# sitrep_display.net
KiCad netlist of a schematic drawn in EAGLE
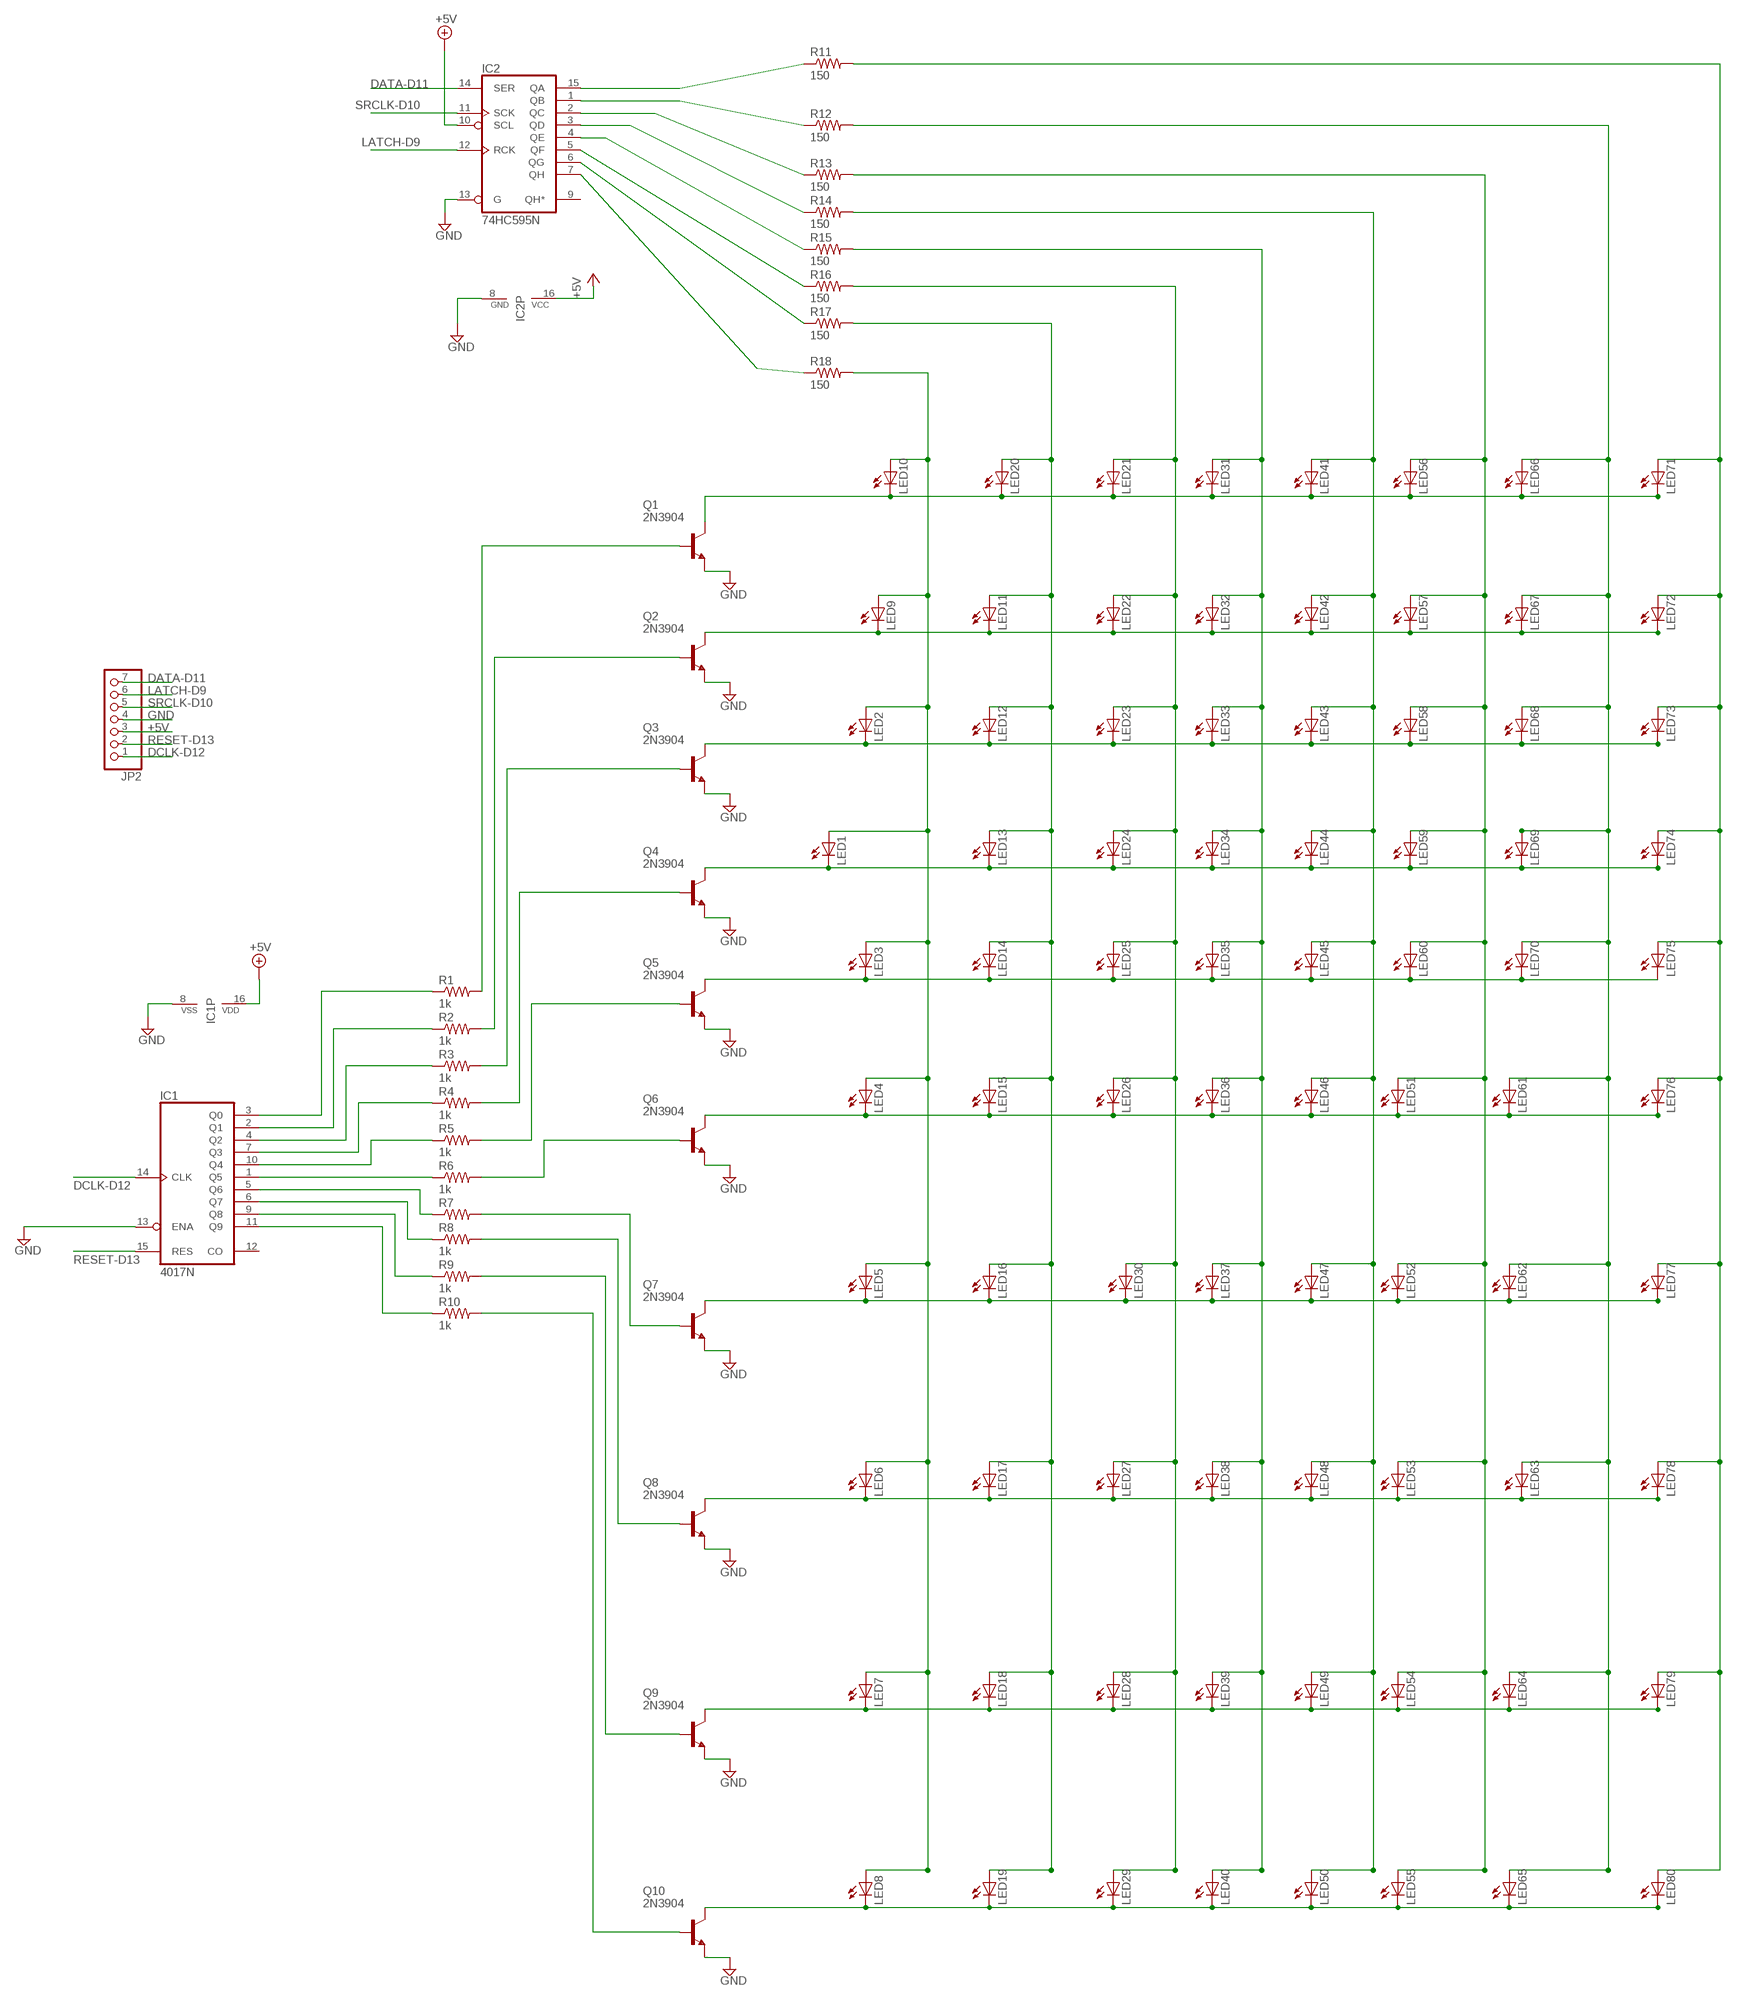
[diagram p0: schematic, sheet 1]

(export (version "E")
  (design (tool "Eeschema 10.0.6"))
  (components
    (comp (ref "IC1")
      (value "4017N")
      (footprint "eagle-import:DIL16")
      (libsource (lib "eagle-import") (part "4017N"))
    )
    (comp (ref "IC2")
      (value "74HC595N")
      (footprint "eagle-import:DIL16")
      (libsource (lib "eagle-import") (part "74595NHC"))
    )
    (comp (ref "JP2")
      (value "PINHD-1X7/90")
      (footprint "eagle-import:1X07_90")
      (libsource (lib "eagle-import") (part "PINHD-1X7/90"))
    )
    (comp (ref "LED1")
      (value "LED5MM")
      (footprint "eagle-import:LED5MM")
      (libsource (lib "eagle-import") (part "LED5MM"))
    )
    (comp (ref "LED2")
      (value "LED5MM")
      (footprint "eagle-import:LED5MM")
      (libsource (lib "eagle-import") (part "LED5MM"))
    )
    (comp (ref "LED3")
      (value "LED5MM")
      (footprint "eagle-import:LED5MM")
      (libsource (lib "eagle-import") (part "LED5MM"))
    )
    (comp (ref "LED4")
      (value "LED5MM")
      (footprint "eagle-import:LED5MM")
      (libsource (lib "eagle-import") (part "LED5MM"))
    )
    (comp (ref "LED5")
      (value "LED5MM")
      (footprint "eagle-import:LED5MM")
      (libsource (lib "eagle-import") (part "LED5MM"))
    )
    (comp (ref "LED6")
      (value "LED5MM")
      (footprint "eagle-import:LED5MM")
      (libsource (lib "eagle-import") (part "LED5MM"))
    )
    (comp (ref "LED7")
      (value "LED5MM")
      (footprint "eagle-import:LED5MM")
      (libsource (lib "eagle-import") (part "LED5MM"))
    )
    (comp (ref "LED8")
      (value "LED5MM")
      (footprint "eagle-import:LED5MM")
      (libsource (lib "eagle-import") (part "LED5MM"))
    )
    (comp (ref "LED9")
      (value "LED5MM")
      (footprint "eagle-import:LED5MM")
      (libsource (lib "eagle-import") (part "LED5MM"))
    )
    (comp (ref "LED10")
      (value "LED5MM")
      (footprint "eagle-import:LED5MM")
      (libsource (lib "eagle-import") (part "LED5MM"))
    )
    (comp (ref "LED11")
      (value "LED5MM")
      (footprint "eagle-import:LED5MM")
      (libsource (lib "eagle-import") (part "LED5MM"))
    )
    (comp (ref "LED12")
      (value "LED5MM")
      (footprint "eagle-import:LED5MM")
      (libsource (lib "eagle-import") (part "LED5MM"))
    )
    (comp (ref "LED13")
      (value "LED5MM")
      (footprint "eagle-import:LED5MM")
      (libsource (lib "eagle-import") (part "LED5MM"))
    )
    (comp (ref "LED14")
      (value "LED5MM")
      (footprint "eagle-import:LED5MM")
      (libsource (lib "eagle-import") (part "LED5MM"))
    )
    (comp (ref "LED15")
      (value "LED5MM")
      (footprint "eagle-import:LED5MM")
      (libsource (lib "eagle-import") (part "LED5MM"))
    )
    (comp (ref "LED16")
      (value "LED5MM")
      (footprint "eagle-import:LED5MM")
      (libsource (lib "eagle-import") (part "LED5MM"))
    )
    (comp (ref "LED17")
      (value "LED5MM")
      (footprint "eagle-import:LED5MM")
      (libsource (lib "eagle-import") (part "LED5MM"))
    )
    (comp (ref "LED18")
      (value "LED5MM")
      (footprint "eagle-import:LED5MM")
      (libsource (lib "eagle-import") (part "LED5MM"))
    )
    (comp (ref "LED19")
      (value "LED5MM")
      (footprint "eagle-import:LED5MM")
      (libsource (lib "eagle-import") (part "LED5MM"))
    )
    (comp (ref "LED20")
      (value "LED5MM")
      (footprint "eagle-import:LED5MM")
      (libsource (lib "eagle-import") (part "LED5MM"))
    )
    (comp (ref "LED21")
      (value "LED5MM")
      (footprint "eagle-import:LED5MM")
      (libsource (lib "eagle-import") (part "LED5MM"))
    )
    (comp (ref "LED22")
      (value "LED5MM")
      (footprint "eagle-import:LED5MM")
      (libsource (lib "eagle-import") (part "LED5MM"))
    )
    (comp (ref "LED23")
      (value "LED5MM")
      (footprint "eagle-import:LED5MM")
      (libsource (lib "eagle-import") (part "LED5MM"))
    )
    (comp (ref "LED24")
      (value "LED5MM")
      (footprint "eagle-import:LED5MM")
      (libsource (lib "eagle-import") (part "LED5MM"))
    )
    (comp (ref "LED25")
      (value "LED5MM")
      (footprint "eagle-import:LED5MM")
      (libsource (lib "eagle-import") (part "LED5MM"))
    )
    (comp (ref "LED26")
      (value "LED5MM")
      (footprint "eagle-import:LED5MM")
      (libsource (lib "eagle-import") (part "LED5MM"))
    )
    (comp (ref "LED27")
      (value "LED5MM")
      (footprint "eagle-import:LED5MM")
      (libsource (lib "eagle-import") (part "LED5MM"))
    )
    (comp (ref "LED28")
      (value "LED5MM")
      (footprint "eagle-import:LED5MM")
      (libsource (lib "eagle-import") (part "LED5MM"))
    )
    (comp (ref "LED29")
      (value "LED5MM")
      (footprint "eagle-import:LED5MM")
      (libsource (lib "eagle-import") (part "LED5MM"))
    )
    (comp (ref "LED30")
      (value "LED5MM")
      (footprint "eagle-import:LED5MM")
      (libsource (lib "eagle-import") (part "LED5MM"))
    )
    (comp (ref "LED31")
      (value "LED5MM")
      (footprint "eagle-import:LED5MM")
      (libsource (lib "eagle-import") (part "LED5MM"))
    )
    (comp (ref "LED32")
      (value "LED5MM")
      (footprint "eagle-import:LED5MM")
      (libsource (lib "eagle-import") (part "LED5MM"))
    )
    (comp (ref "LED33")
      (value "LED5MM")
      (footprint "eagle-import:LED5MM")
      (libsource (lib "eagle-import") (part "LED5MM"))
    )
    (comp (ref "LED34")
      (value "LED5MM")
      (footprint "eagle-import:LED5MM")
      (libsource (lib "eagle-import") (part "LED5MM"))
    )
    (comp (ref "LED35")
      (value "LED5MM")
      (footprint "eagle-import:LED5MM")
      (libsource (lib "eagle-import") (part "LED5MM"))
    )
    (comp (ref "LED36")
      (value "LED5MM")
      (footprint "eagle-import:LED5MM")
      (libsource (lib "eagle-import") (part "LED5MM"))
    )
    (comp (ref "LED37")
      (value "LED5MM")
      (footprint "eagle-import:LED5MM")
      (libsource (lib "eagle-import") (part "LED5MM"))
    )
    (comp (ref "LED38")
      (value "LED5MM")
      (footprint "eagle-import:LED5MM")
      (libsource (lib "eagle-import") (part "LED5MM"))
    )
    (comp (ref "LED39")
      (value "LED5MM")
      (footprint "eagle-import:LED5MM")
      (libsource (lib "eagle-import") (part "LED5MM"))
    )
    (comp (ref "LED40")
      (value "LED5MM")
      (footprint "eagle-import:LED5MM")
      (libsource (lib "eagle-import") (part "LED5MM"))
    )
    (comp (ref "LED41")
      (value "LED5MM")
      (footprint "eagle-import:LED5MM")
      (libsource (lib "eagle-import") (part "LED5MM"))
    )
    (comp (ref "LED42")
      (value "LED5MM")
      (footprint "eagle-import:LED5MM")
      (libsource (lib "eagle-import") (part "LED5MM"))
    )
    (comp (ref "LED43")
      (value "LED5MM")
      (footprint "eagle-import:LED5MM")
      (libsource (lib "eagle-import") (part "LED5MM"))
    )
    (comp (ref "LED44")
      (value "LED5MM")
      (footprint "eagle-import:LED5MM")
      (libsource (lib "eagle-import") (part "LED5MM"))
    )
    (comp (ref "LED45")
      (value "LED5MM")
      (footprint "eagle-import:LED5MM")
      (libsource (lib "eagle-import") (part "LED5MM"))
    )
    (comp (ref "LED46")
      (value "LED5MM")
      (footprint "eagle-import:LED5MM")
      (libsource (lib "eagle-import") (part "LED5MM"))
    )
    (comp (ref "LED47")
      (value "LED5MM")
      (footprint "eagle-import:LED5MM")
      (libsource (lib "eagle-import") (part "LED5MM"))
    )
    (comp (ref "LED48")
      (value "LED5MM")
      (footprint "eagle-import:LED5MM")
      (libsource (lib "eagle-import") (part "LED5MM"))
    )
    (comp (ref "LED49")
      (value "LED5MM")
      (footprint "eagle-import:LED5MM")
      (libsource (lib "eagle-import") (part "LED5MM"))
    )
    (comp (ref "LED50")
      (value "LED5MM")
      (footprint "eagle-import:LED5MM")
      (libsource (lib "eagle-import") (part "LED5MM"))
    )
    (comp (ref "LED51")
      (value "LED5MM")
      (footprint "eagle-import:LED5MM")
      (libsource (lib "eagle-import") (part "LED5MM"))
    )
    (comp (ref "LED52")
      (value "LED5MM")
      (footprint "eagle-import:LED5MM")
      (libsource (lib "eagle-import") (part "LED5MM"))
    )
    (comp (ref "LED53")
      (value "LED5MM")
      (footprint "eagle-import:LED5MM")
      (libsource (lib "eagle-import") (part "LED5MM"))
    )
    (comp (ref "LED54")
      (value "LED5MM")
      (footprint "eagle-import:LED5MM")
      (libsource (lib "eagle-import") (part "LED5MM"))
    )
    (comp (ref "LED55")
      (value "LED5MM")
      (footprint "eagle-import:LED5MM")
      (libsource (lib "eagle-import") (part "LED5MM"))
    )
    (comp (ref "LED56")
      (value "LED5MM")
      (footprint "eagle-import:LED5MM")
      (libsource (lib "eagle-import") (part "LED5MM"))
    )
    (comp (ref "LED57")
      (value "LED5MM")
      (footprint "eagle-import:LED5MM")
      (libsource (lib "eagle-import") (part "LED5MM"))
    )
    (comp (ref "LED58")
      (value "LED5MM")
      (footprint "eagle-import:LED5MM")
      (libsource (lib "eagle-import") (part "LED5MM"))
    )
    (comp (ref "LED59")
      (value "LED5MM")
      (footprint "eagle-import:LED5MM")
      (libsource (lib "eagle-import") (part "LED5MM"))
    )
    (comp (ref "LED60")
      (value "LED5MM")
      (footprint "eagle-import:LED5MM")
      (libsource (lib "eagle-import") (part "LED5MM"))
    )
    (comp (ref "LED61")
      (value "LED5MM")
      (footprint "eagle-import:LED5MM")
      (libsource (lib "eagle-import") (part "LED5MM"))
    )
    (comp (ref "LED62")
      (value "LED5MM")
      (footprint "eagle-import:LED5MM")
      (libsource (lib "eagle-import") (part "LED5MM"))
    )
    (comp (ref "LED63")
      (value "LED5MM")
      (footprint "eagle-import:LED5MM")
      (libsource (lib "eagle-import") (part "LED5MM"))
    )
    (comp (ref "LED64")
      (value "LED5MM")
      (footprint "eagle-import:LED5MM")
      (libsource (lib "eagle-import") (part "LED5MM"))
    )
    (comp (ref "LED65")
      (value "LED5MM")
      (footprint "eagle-import:LED5MM")
      (libsource (lib "eagle-import") (part "LED5MM"))
    )
    (comp (ref "LED66")
      (value "LED5MM")
      (footprint "eagle-import:LED5MM")
      (libsource (lib "eagle-import") (part "LED5MM"))
    )
    (comp (ref "LED67")
      (value "LED5MM")
      (footprint "eagle-import:LED5MM")
      (libsource (lib "eagle-import") (part "LED5MM"))
    )
    (comp (ref "LED68")
      (value "LED5MM")
      (footprint "eagle-import:LED5MM")
      (libsource (lib "eagle-import") (part "LED5MM"))
    )
    (comp (ref "LED69")
      (value "LED5MM")
      (footprint "eagle-import:LED5MM")
      (libsource (lib "eagle-import") (part "LED5MM"))
    )
    (comp (ref "LED70")
      (value "LED5MM")
      (footprint "eagle-import:LED5MM")
      (libsource (lib "eagle-import") (part "LED5MM"))
    )
    (comp (ref "LED71")
      (value "LED5MM")
      (footprint "eagle-import:LED5MM")
      (libsource (lib "eagle-import") (part "LED5MM"))
    )
    (comp (ref "LED72")
      (value "LED5MM")
      (footprint "eagle-import:LED5MM")
      (libsource (lib "eagle-import") (part "LED5MM"))
    )
    (comp (ref "LED73")
      (value "LED5MM")
      (footprint "eagle-import:LED5MM")
      (libsource (lib "eagle-import") (part "LED5MM"))
    )
    (comp (ref "LED74")
      (value "LED5MM")
      (footprint "eagle-import:LED5MM")
      (libsource (lib "eagle-import") (part "LED5MM"))
    )
    (comp (ref "LED75")
      (value "LED5MM")
      (footprint "eagle-import:LED5MM")
      (libsource (lib "eagle-import") (part "LED5MM"))
    )
    (comp (ref "LED76")
      (value "LED5MM")
      (footprint "eagle-import:LED5MM")
      (libsource (lib "eagle-import") (part "LED5MM"))
    )
    (comp (ref "LED77")
      (value "LED5MM")
      (footprint "eagle-import:LED5MM")
      (libsource (lib "eagle-import") (part "LED5MM"))
    )
    (comp (ref "LED78")
      (value "LED5MM")
      (footprint "eagle-import:LED5MM")
      (libsource (lib "eagle-import") (part "LED5MM"))
    )
    (comp (ref "LED79")
      (value "LED5MM")
      (footprint "eagle-import:LED5MM")
      (libsource (lib "eagle-import") (part "LED5MM"))
    )
    (comp (ref "LED80")
      (value "LED5MM")
      (footprint "eagle-import:LED5MM")
      (libsource (lib "eagle-import") (part "LED5MM"))
    )
    (comp (ref "Q1")
      (value "2N3904")
      (footprint "eagle-import:TO92")
      (libsource (lib "eagle-import") (part "2N3904"))
    )
    (comp (ref "Q2")
      (value "2N3904")
      (footprint "eagle-import:TO92")
      (libsource (lib "eagle-import") (part "2N3904"))
    )
    (comp (ref "Q3")
      (value "2N3904")
      (footprint "eagle-import:TO92")
      (libsource (lib "eagle-import") (part "2N3904"))
    )
    (comp (ref "Q4")
      (value "2N3904")
      (footprint "eagle-import:TO92")
      (libsource (lib "eagle-import") (part "2N3904"))
    )
    (comp (ref "Q5")
      (value "2N3904")
      (footprint "eagle-import:TO92")
      (libsource (lib "eagle-import") (part "2N3904"))
    )
    (comp (ref "Q6")
      (value "2N3904")
      (footprint "eagle-import:TO92")
      (libsource (lib "eagle-import") (part "2N3904"))
    )
    (comp (ref "Q7")
      (value "2N3904")
      (footprint "eagle-import:TO92")
      (libsource (lib "eagle-import") (part "2N3904"))
    )
    (comp (ref "Q8")
      (value "2N3904")
      (footprint "eagle-import:TO92")
      (libsource (lib "eagle-import") (part "2N3904"))
    )
    (comp (ref "Q9")
      (value "2N3904")
      (footprint "eagle-import:TO92")
      (libsource (lib "eagle-import") (part "2N3904"))
    )
    (comp (ref "Q10")
      (value "2N3904")
      (footprint "eagle-import:TO92")
      (libsource (lib "eagle-import") (part "2N3904"))
    )
    (comp (ref "R1")
      (value "1k")
      (footprint "eagle-import:0204V")
      (libsource (lib "eagle-import") (part "resistor_R-US_0204/2V"))
    )
    (comp (ref "R2")
      (value "1k")
      (footprint "eagle-import:0204V")
      (libsource (lib "eagle-import") (part "resistor_R-US_0204/2V"))
    )
    (comp (ref "R3")
      (value "1k")
      (footprint "eagle-import:0204V")
      (libsource (lib "eagle-import") (part "resistor_R-US_0204/2V"))
    )
    (comp (ref "R4")
      (value "1k")
      (footprint "eagle-import:0204V")
      (libsource (lib "eagle-import") (part "resistor_R-US_0204/2V"))
    )
    (comp (ref "R5")
      (value "1k")
      (footprint "eagle-import:0204V")
      (libsource (lib "eagle-import") (part "resistor_R-US_0204/2V"))
    )
    (comp (ref "R6")
      (value "1k")
      (footprint "eagle-import:0204V")
      (libsource (lib "eagle-import") (part "resistor_R-US_0204/2V"))
    )
    (comp (ref "R7")
      (value "R-US_0204/2V")
      (footprint "eagle-import:0204V")
      (libsource (lib "eagle-import") (part "resistor_R-US_0204/2V"))
    )
    (comp (ref "R8")
      (value "1k")
      (footprint "eagle-import:0204V")
      (libsource (lib "eagle-import") (part "resistor_R-US_0204/2V"))
    )
    (comp (ref "R9")
      (value "1k")
      (footprint "eagle-import:0204V")
      (libsource (lib "eagle-import") (part "resistor_R-US_0204/2V"))
    )
    (comp (ref "R10")
      (value "1k")
      (footprint "eagle-import:0204V")
      (libsource (lib "eagle-import") (part "resistor_R-US_0204/2V"))
    )
    (comp (ref "R11")
      (value "150")
      (footprint "eagle-import:0207_2V")
      (libsource (lib "eagle-import") (part "R-US_0207/2V"))
    )
    (comp (ref "R12")
      (value "150")
      (footprint "eagle-import:0207_2V")
      (libsource (lib "eagle-import") (part "R-US_0207/2V"))
    )
    (comp (ref "R13")
      (value "150")
      (footprint "eagle-import:0207_2V")
      (libsource (lib "eagle-import") (part "R-US_0207/2V"))
    )
    (comp (ref "R14")
      (value "150")
      (footprint "eagle-import:0207_2V")
      (libsource (lib "eagle-import") (part "R-US_0207/2V"))
    )
    (comp (ref "R15")
      (value "150")
      (footprint "eagle-import:0207_2V")
      (libsource (lib "eagle-import") (part "R-US_0207/2V"))
    )
    (comp (ref "R16")
      (value "150")
      (footprint "eagle-import:0207_2V")
      (libsource (lib "eagle-import") (part "R-US_0207/2V"))
    )
    (comp (ref "R17")
      (value "150")
      (footprint "eagle-import:0207_2V")
      (libsource (lib "eagle-import") (part "R-US_0207/2V"))
    )
    (comp (ref "R18")
      (value "150")
      (footprint "eagle-import:0207_2V")
      (libsource (lib "eagle-import") (part "R-US_0207/2V"))
    )
  )
  (nets
    (net (code "1") (name "+5V") (class "Default")
      (node (ref "IC1") (pin "16") (pinfunction "VDD_16") (pintype "power_in"))
      (node (ref "IC2") (pin "10") (pinfunction "SCL_10") (pintype "input"))
      (node (ref "IC2") (pin "16") (pinfunction "VCC_16") (pintype "power_in"))
      (node (ref "JP2") (pin "3") (pinfunction "3_3") (pintype "passive"))
    )
    (net (code "2") (name "/DATA-D11") (class "Default")
      (node (ref "IC2") (pin "14") (pinfunction "SER_14") (pintype "input"))
      (node (ref "JP2") (pin "7") (pinfunction "7_7") (pintype "passive"))
    )
    (net (code "3") (name "/DCLK-D12") (class "Default")
      (node (ref "IC1") (pin "14") (pinfunction "CLK_14") (pintype "input"))
      (node (ref "JP2") (pin "1") (pinfunction "1_1") (pintype "passive"))
    )
    (net (code "4") (name "/LATCH-D9") (class "Default")
      (node (ref "IC2") (pin "12") (pinfunction "RCK_12") (pintype "input"))
      (node (ref "JP2") (pin "6") (pinfunction "6_6") (pintype "passive"))
    )
    (net (code "5") (name "/RESET-D13") (class "Default")
      (node (ref "IC1") (pin "15") (pinfunction "RES_15") (pintype "input"))
      (node (ref "JP2") (pin "2") (pinfunction "2_2") (pintype "passive"))
    )
    (net (code "6") (name "/SRCLK-D10") (class "Default")
      (node (ref "IC2") (pin "11") (pinfunction "SCK_11") (pintype "input"))
      (node (ref "JP2") (pin "5") (pinfunction "5_5") (pintype "passive"))
    )
    (net (code "7") (name "GND") (class "Default")
      (node (ref "IC1") (pin "13") (pinfunction "ENA_13") (pintype "input"))
      (node (ref "IC1") (pin "8") (pinfunction "VSS_8") (pintype "power_in"))
      (node (ref "IC2") (pin "13") (pinfunction "G_13") (pintype "input"))
      (node (ref "IC2") (pin "8") (pinfunction "GND_8") (pintype "power_in"))
      (node (ref "JP2") (pin "4") (pinfunction "4_4") (pintype "passive"))
      (node (ref "Q1") (pin "3") (pinfunction "E_3") (pintype "passive"))
      (node (ref "Q10") (pin "3") (pinfunction "E_3") (pintype "passive"))
      (node (ref "Q2") (pin "3") (pinfunction "E_3") (pintype "passive"))
      (node (ref "Q3") (pin "3") (pinfunction "E_3") (pintype "passive"))
      (node (ref "Q4") (pin "3") (pinfunction "E_3") (pintype "passive"))
      (node (ref "Q5") (pin "3") (pinfunction "E_3") (pintype "passive"))
      (node (ref "Q6") (pin "3") (pinfunction "E_3") (pintype "passive"))
      (node (ref "Q7") (pin "3") (pinfunction "E_3") (pintype "passive"))
      (node (ref "Q8") (pin "3") (pinfunction "E_3") (pintype "passive"))
      (node (ref "Q9") (pin "3") (pinfunction "E_3") (pintype "passive"))
    )
    (net (code "8") (name "Net-(IC1A-Q0)") (class "Default")
      (node (ref "IC1") (pin "3") (pinfunction "Q0_3") (pintype "output"))
      (node (ref "R1") (pin "1") (pinfunction "1_1") (pintype "passive"))
    )
    (net (code "9") (name "Net-(IC1A-Q1)") (class "Default")
      (node (ref "IC1") (pin "2") (pinfunction "Q1_2") (pintype "output"))
      (node (ref "R2") (pin "1") (pinfunction "1_1") (pintype "passive"))
    )
    (net (code "10") (name "Net-(IC1A-Q2)") (class "Default")
      (node (ref "IC1") (pin "4") (pinfunction "Q2_4") (pintype "output"))
      (node (ref "R3") (pin "1") (pinfunction "1_1") (pintype "passive"))
    )
    (net (code "11") (name "Net-(IC1A-Q3)") (class "Default")
      (node (ref "IC1") (pin "7") (pinfunction "Q3_7") (pintype "output"))
      (node (ref "R4") (pin "1") (pinfunction "1_1") (pintype "passive"))
    )
    (net (code "12") (name "Net-(IC1A-Q4)") (class "Default")
      (node (ref "IC1") (pin "10") (pinfunction "Q4_10") (pintype "output"))
      (node (ref "R5") (pin "1") (pinfunction "1_1") (pintype "passive"))
    )
    (net (code "13") (name "Net-(IC1A-Q5)") (class "Default")
      (node (ref "IC1") (pin "1") (pinfunction "Q5_1") (pintype "output"))
      (node (ref "R6") (pin "1") (pinfunction "1_1") (pintype "passive"))
    )
    (net (code "14") (name "Net-(IC1A-Q6)") (class "Default")
      (node (ref "IC1") (pin "5") (pinfunction "Q6_5") (pintype "output"))
      (node (ref "R7") (pin "1") (pinfunction "1_1") (pintype "passive"))
    )
    (net (code "15") (name "Net-(IC1A-Q7)") (class "Default")
      (node (ref "IC1") (pin "6") (pinfunction "Q7_6") (pintype "output"))
      (node (ref "R8") (pin "1") (pinfunction "1_1") (pintype "passive"))
    )
    (net (code "16") (name "Net-(IC1A-Q8)") (class "Default")
      (node (ref "IC1") (pin "9") (pinfunction "Q8_9") (pintype "output"))
      (node (ref "R9") (pin "1") (pinfunction "1_1") (pintype "passive"))
    )
    (net (code "17") (name "Net-(IC1A-Q9)") (class "Default")
      (node (ref "IC1") (pin "11") (pinfunction "Q9_11") (pintype "output"))
      (node (ref "R10") (pin "1") (pinfunction "1_1") (pintype "passive"))
    )
    (net (code "18") (name "Net-(IC2A-QA)") (class "Default")
      (node (ref "IC2") (pin "15") (pinfunction "QA_15") (pintype "tri_state"))
      (node (ref "R11") (pin "1") (pinfunction "1_1") (pintype "passive"))
    )
    (net (code "19") (name "Net-(IC2A-QB)") (class "Default")
      (node (ref "IC2") (pin "1") (pinfunction "QB_1") (pintype "tri_state"))
      (node (ref "R12") (pin "1") (pinfunction "1_1") (pintype "passive"))
    )
    (net (code "20") (name "Net-(IC2A-QC)") (class "Default")
      (node (ref "IC2") (pin "2") (pinfunction "QC_2") (pintype "tri_state"))
      (node (ref "R13") (pin "1") (pinfunction "1_1") (pintype "passive"))
    )
    (net (code "21") (name "Net-(IC2A-QD)") (class "Default")
      (node (ref "IC2") (pin "3") (pinfunction "QD_3") (pintype "tri_state"))
      (node (ref "R14") (pin "1") (pinfunction "1_1") (pintype "passive"))
    )
    (net (code "22") (name "Net-(IC2A-QE)") (class "Default")
      (node (ref "IC2") (pin "4") (pinfunction "QE_4") (pintype "tri_state"))
      (node (ref "R15") (pin "1") (pinfunction "1_1") (pintype "passive"))
    )
    (net (code "23") (name "Net-(IC2A-QF)") (class "Default")
      (node (ref "IC2") (pin "5") (pinfunction "QF_5") (pintype "tri_state"))
      (node (ref "R16") (pin "1") (pinfunction "1_1") (pintype "passive"))
    )
    (net (code "24") (name "Net-(IC2A-QG)") (class "Default")
      (node (ref "IC2") (pin "6") (pinfunction "QG_6") (pintype "tri_state"))
      (node (ref "R17") (pin "1") (pinfunction "1_1") (pintype "passive"))
    )
    (net (code "25") (name "Net-(IC2A-QH)") (class "Default")
      (node (ref "IC2") (pin "7") (pinfunction "QH_7") (pintype "tri_state"))
      (node (ref "R18") (pin "1") (pinfunction "1_1") (pintype "passive"))
    )
    (net (code "26") (name "Net-(LED1-C)") (class "Default")
      (node (ref "LED1") (pin "K") (pinfunction "C_K") (pintype "passive"))
      (node (ref "LED13") (pin "K") (pinfunction "C_K") (pintype "passive"))
      (node (ref "LED24") (pin "K") (pinfunction "C_K") (pintype "passive"))
      (node (ref "LED34") (pin "K") (pinfunction "C_K") (pintype "passive"))
      (node (ref "LED44") (pin "K") (pinfunction "C_K") (pintype "passive"))
      (node (ref "LED59") (pin "K") (pinfunction "C_K") (pintype "passive"))
      (node (ref "LED69") (pin "K") (pinfunction "C_K") (pintype "passive"))
      (node (ref "LED74") (pin "K") (pinfunction "C_K") (pintype "passive"))
      (node (ref "Q4") (pin "1") (pinfunction "C_1") (pintype "passive"))
    )
    (net (code "27") (name "Net-(LED1-PadA)") (class "Default")
      (node (ref "LED1") (pin "A") (pinfunction "A_A") (pintype "passive"))
      (node (ref "LED10") (pin "A") (pinfunction "A_A") (pintype "passive"))
      (node (ref "LED2") (pin "A") (pinfunction "A_A") (pintype "passive"))
      (node (ref "LED3") (pin "A") (pinfunction "A_A") (pintype "passive"))
      (node (ref "LED4") (pin "A") (pinfunction "A_A") (pintype "passive"))
      (node (ref "LED5") (pin "A") (pinfunction "A_A") (pintype "passive"))
      (node (ref "LED6") (pin "A") (pinfunction "A_A") (pintype "passive"))
      (node (ref "LED7") (pin "A") (pinfunction "A_A") (pintype "passive"))
      (node (ref "LED8") (pin "A") (pinfunction "A_A") (pintype "passive"))
      (node (ref "LED9") (pin "A") (pinfunction "A_A") (pintype "passive"))
      (node (ref "R18") (pin "2") (pinfunction "2_2") (pintype "passive"))
    )
    (net (code "28") (name "Net-(LED10-C)") (class "Default")
      (node (ref "LED10") (pin "K") (pinfunction "C_K") (pintype "passive"))
      (node (ref "LED20") (pin "K") (pinfunction "C_K") (pintype "passive"))
      (node (ref "LED21") (pin "K") (pinfunction "C_K") (pintype "passive"))
      (node (ref "LED31") (pin "K") (pinfunction "C_K") (pintype "passive"))
      (node (ref "LED41") (pin "K") (pinfunction "C_K") (pintype "passive"))
      (node (ref "LED56") (pin "K") (pinfunction "C_K") (pintype "passive"))
      (node (ref "LED66") (pin "K") (pinfunction "C_K") (pintype "passive"))
      (node (ref "LED71") (pin "K") (pinfunction "C_K") (pintype "passive"))
      (node (ref "Q1") (pin "1") (pinfunction "C_1") (pintype "passive"))
    )
    (net (code "29") (name "Net-(LED11-C)") (class "Default")
      (node (ref "LED11") (pin "K") (pinfunction "C_K") (pintype "passive"))
      (node (ref "LED22") (pin "K") (pinfunction "C_K") (pintype "passive"))
      (node (ref "LED32") (pin "K") (pinfunction "C_K") (pintype "passive"))
      (node (ref "LED42") (pin "K") (pinfunction "C_K") (pintype "passive"))
      (node (ref "LED57") (pin "K") (pinfunction "C_K") (pintype "passive"))
      (node (ref "LED67") (pin "K") (pinfunction "C_K") (pintype "passive"))
      (node (ref "LED72") (pin "K") (pinfunction "C_K") (pintype "passive"))
      (node (ref "LED9") (pin "K") (pinfunction "C_K") (pintype "passive"))
      (node (ref "Q2") (pin "1") (pinfunction "C_1") (pintype "passive"))
    )
    (net (code "30") (name "Net-(LED11-PadA)") (class "Default")
      (node (ref "LED11") (pin "A") (pinfunction "A_A") (pintype "passive"))
      (node (ref "LED12") (pin "A") (pinfunction "A_A") (pintype "passive"))
      (node (ref "LED13") (pin "A") (pinfunction "A_A") (pintype "passive"))
      (node (ref "LED14") (pin "A") (pinfunction "A_A") (pintype "passive"))
      (node (ref "LED15") (pin "A") (pinfunction "A_A") (pintype "passive"))
      (node (ref "LED16") (pin "A") (pinfunction "A_A") (pintype "passive"))
      (node (ref "LED17") (pin "A") (pinfunction "A_A") (pintype "passive"))
      (node (ref "LED18") (pin "A") (pinfunction "A_A") (pintype "passive"))
      (node (ref "LED19") (pin "A") (pinfunction "A_A") (pintype "passive"))
      (node (ref "LED20") (pin "A") (pinfunction "A_A") (pintype "passive"))
      (node (ref "R17") (pin "2") (pinfunction "2_2") (pintype "passive"))
    )
    (net (code "31") (name "Net-(LED12-C)") (class "Default")
      (node (ref "LED12") (pin "K") (pinfunction "C_K") (pintype "passive"))
      (node (ref "LED2") (pin "K") (pinfunction "C_K") (pintype "passive"))
      (node (ref "LED23") (pin "K") (pinfunction "C_K") (pintype "passive"))
      (node (ref "LED33") (pin "K") (pinfunction "C_K") (pintype "passive"))
      (node (ref "LED43") (pin "K") (pinfunction "C_K") (pintype "passive"))
      (node (ref "LED58") (pin "K") (pinfunction "C_K") (pintype "passive"))
      (node (ref "LED68") (pin "K") (pinfunction "C_K") (pintype "passive"))
      (node (ref "LED73") (pin "K") (pinfunction "C_K") (pintype "passive"))
      (node (ref "Q3") (pin "1") (pinfunction "C_1") (pintype "passive"))
    )
    (net (code "32") (name "Net-(LED14-C)") (class "Default")
      (node (ref "LED14") (pin "K") (pinfunction "C_K") (pintype "passive"))
      (node (ref "LED25") (pin "K") (pinfunction "C_K") (pintype "passive"))
      (node (ref "LED3") (pin "K") (pinfunction "C_K") (pintype "passive"))
      (node (ref "LED35") (pin "K") (pinfunction "C_K") (pintype "passive"))
      (node (ref "LED45") (pin "K") (pinfunction "C_K") (pintype "passive"))
      (node (ref "LED60") (pin "K") (pinfunction "C_K") (pintype "passive"))
      (node (ref "LED70") (pin "K") (pinfunction "C_K") (pintype "passive"))
      (node (ref "LED75") (pin "K") (pinfunction "C_K") (pintype "passive"))
      (node (ref "Q5") (pin "1") (pinfunction "C_1") (pintype "passive"))
    )
    (net (code "33") (name "Net-(LED15-C)") (class "Default")
      (node (ref "LED15") (pin "K") (pinfunction "C_K") (pintype "passive"))
      (node (ref "LED26") (pin "K") (pinfunction "C_K") (pintype "passive"))
      (node (ref "LED36") (pin "K") (pinfunction "C_K") (pintype "passive"))
      (node (ref "LED4") (pin "K") (pinfunction "C_K") (pintype "passive"))
      (node (ref "LED46") (pin "K") (pinfunction "C_K") (pintype "passive"))
      (node (ref "LED51") (pin "K") (pinfunction "C_K") (pintype "passive"))
      (node (ref "LED61") (pin "K") (pinfunction "C_K") (pintype "passive"))
      (node (ref "LED76") (pin "K") (pinfunction "C_K") (pintype "passive"))
      (node (ref "Q6") (pin "1") (pinfunction "C_1") (pintype "passive"))
    )
    (net (code "34") (name "Net-(LED16-C)") (class "Default")
      (node (ref "LED16") (pin "K") (pinfunction "C_K") (pintype "passive"))
      (node (ref "LED30") (pin "K") (pinfunction "C_K") (pintype "passive"))
      (node (ref "LED37") (pin "K") (pinfunction "C_K") (pintype "passive"))
      (node (ref "LED47") (pin "K") (pinfunction "C_K") (pintype "passive"))
      (node (ref "LED5") (pin "K") (pinfunction "C_K") (pintype "passive"))
      (node (ref "LED52") (pin "K") (pinfunction "C_K") (pintype "passive"))
      (node (ref "LED62") (pin "K") (pinfunction "C_K") (pintype "passive"))
      (node (ref "LED77") (pin "K") (pinfunction "C_K") (pintype "passive"))
      (node (ref "Q7") (pin "1") (pinfunction "C_1") (pintype "passive"))
    )
    (net (code "35") (name "Net-(LED17-C)") (class "Default")
      (node (ref "LED17") (pin "K") (pinfunction "C_K") (pintype "passive"))
      (node (ref "LED27") (pin "K") (pinfunction "C_K") (pintype "passive"))
      (node (ref "LED38") (pin "K") (pinfunction "C_K") (pintype "passive"))
      (node (ref "LED48") (pin "K") (pinfunction "C_K") (pintype "passive"))
      (node (ref "LED53") (pin "K") (pinfunction "C_K") (pintype "passive"))
      (node (ref "LED6") (pin "K") (pinfunction "C_K") (pintype "passive"))
      (node (ref "LED63") (pin "K") (pinfunction "C_K") (pintype "passive"))
      (node (ref "LED78") (pin "K") (pinfunction "C_K") (pintype "passive"))
      (node (ref "Q8") (pin "1") (pinfunction "C_1") (pintype "passive"))
    )
    (net (code "36") (name "Net-(LED18-C)") (class "Default")
      (node (ref "LED18") (pin "K") (pinfunction "C_K") (pintype "passive"))
      (node (ref "LED28") (pin "K") (pinfunction "C_K") (pintype "passive"))
      (node (ref "LED39") (pin "K") (pinfunction "C_K") (pintype "passive"))
      (node (ref "LED49") (pin "K") (pinfunction "C_K") (pintype "passive"))
      (node (ref "LED54") (pin "K") (pinfunction "C_K") (pintype "passive"))
      (node (ref "LED64") (pin "K") (pinfunction "C_K") (pintype "passive"))
      (node (ref "LED7") (pin "K") (pinfunction "C_K") (pintype "passive"))
      (node (ref "LED79") (pin "K") (pinfunction "C_K") (pintype "passive"))
      (node (ref "Q9") (pin "1") (pinfunction "C_1") (pintype "passive"))
    )
    (net (code "37") (name "Net-(LED19-C)") (class "Default")
      (node (ref "LED19") (pin "K") (pinfunction "C_K") (pintype "passive"))
      (node (ref "LED29") (pin "K") (pinfunction "C_K") (pintype "passive"))
      (node (ref "LED40") (pin "K") (pinfunction "C_K") (pintype "passive"))
      (node (ref "LED50") (pin "K") (pinfunction "C_K") (pintype "passive"))
      (node (ref "LED55") (pin "K") (pinfunction "C_K") (pintype "passive"))
      (node (ref "LED65") (pin "K") (pinfunction "C_K") (pintype "passive"))
      (node (ref "LED8") (pin "K") (pinfunction "C_K") (pintype "passive"))
      (node (ref "LED80") (pin "K") (pinfunction "C_K") (pintype "passive"))
      (node (ref "Q10") (pin "1") (pinfunction "C_1") (pintype "passive"))
    )
    (net (code "38") (name "Net-(LED21-PadA)") (class "Default")
      (node (ref "LED21") (pin "A") (pinfunction "A_A") (pintype "passive"))
      (node (ref "LED22") (pin "A") (pinfunction "A_A") (pintype "passive"))
      (node (ref "LED23") (pin "A") (pinfunction "A_A") (pintype "passive"))
      (node (ref "LED24") (pin "A") (pinfunction "A_A") (pintype "passive"))
      (node (ref "LED25") (pin "A") (pinfunction "A_A") (pintype "passive"))
      (node (ref "LED26") (pin "A") (pinfunction "A_A") (pintype "passive"))
      (node (ref "LED27") (pin "A") (pinfunction "A_A") (pintype "passive"))
      (node (ref "LED28") (pin "A") (pinfunction "A_A") (pintype "passive"))
      (node (ref "LED29") (pin "A") (pinfunction "A_A") (pintype "passive"))
      (node (ref "LED30") (pin "A") (pinfunction "A_A") (pintype "passive"))
      (node (ref "R16") (pin "2") (pinfunction "2_2") (pintype "passive"))
    )
    (net (code "39") (name "Net-(LED31-PadA)") (class "Default")
      (node (ref "LED31") (pin "A") (pinfunction "A_A") (pintype "passive"))
      (node (ref "LED32") (pin "A") (pinfunction "A_A") (pintype "passive"))
      (node (ref "LED33") (pin "A") (pinfunction "A_A") (pintype "passive"))
      (node (ref "LED34") (pin "A") (pinfunction "A_A") (pintype "passive"))
      (node (ref "LED35") (pin "A") (pinfunction "A_A") (pintype "passive"))
      (node (ref "LED36") (pin "A") (pinfunction "A_A") (pintype "passive"))
      (node (ref "LED37") (pin "A") (pinfunction "A_A") (pintype "passive"))
      (node (ref "LED38") (pin "A") (pinfunction "A_A") (pintype "passive"))
      (node (ref "LED39") (pin "A") (pinfunction "A_A") (pintype "passive"))
      (node (ref "LED40") (pin "A") (pinfunction "A_A") (pintype "passive"))
      (node (ref "R15") (pin "2") (pinfunction "2_2") (pintype "passive"))
    )
    (net (code "40") (name "Net-(LED41-PadA)") (class "Default")
      (node (ref "LED41") (pin "A") (pinfunction "A_A") (pintype "passive"))
      (node (ref "LED42") (pin "A") (pinfunction "A_A") (pintype "passive"))
      (node (ref "LED43") (pin "A") (pinfunction "A_A") (pintype "passive"))
      (node (ref "LED44") (pin "A") (pinfunction "A_A") (pintype "passive"))
      (node (ref "LED45") (pin "A") (pinfunction "A_A") (pintype "passive"))
      (node (ref "LED46") (pin "A") (pinfunction "A_A") (pintype "passive"))
      (node (ref "LED47") (pin "A") (pinfunction "A_A") (pintype "passive"))
      (node (ref "LED48") (pin "A") (pinfunction "A_A") (pintype "passive"))
      (node (ref "LED49") (pin "A") (pinfunction "A_A") (pintype "passive"))
      (node (ref "LED50") (pin "A") (pinfunction "A_A") (pintype "passive"))
      (node (ref "R14") (pin "2") (pinfunction "2_2") (pintype "passive"))
    )
    (net (code "41") (name "Net-(LED51-PadA)") (class "Default")
      (node (ref "LED51") (pin "A") (pinfunction "A_A") (pintype "passive"))
      (node (ref "LED52") (pin "A") (pinfunction "A_A") (pintype "passive"))
      (node (ref "LED53") (pin "A") (pinfunction "A_A") (pintype "passive"))
      (node (ref "LED54") (pin "A") (pinfunction "A_A") (pintype "passive"))
      (node (ref "LED55") (pin "A") (pinfunction "A_A") (pintype "passive"))
      (node (ref "LED56") (pin "A") (pinfunction "A_A") (pintype "passive"))
      (node (ref "LED57") (pin "A") (pinfunction "A_A") (pintype "passive"))
      (node (ref "LED58") (pin "A") (pinfunction "A_A") (pintype "passive"))
      (node (ref "LED59") (pin "A") (pinfunction "A_A") (pintype "passive"))
      (node (ref "LED60") (pin "A") (pinfunction "A_A") (pintype "passive"))
      (node (ref "R13") (pin "2") (pinfunction "2_2") (pintype "passive"))
    )
    (net (code "42") (name "Net-(LED61-PadA)") (class "Default")
      (node (ref "LED61") (pin "A") (pinfunction "A_A") (pintype "passive"))
      (node (ref "LED62") (pin "A") (pinfunction "A_A") (pintype "passive"))
      (node (ref "LED63") (pin "A") (pinfunction "A_A") (pintype "passive"))
      (node (ref "LED64") (pin "A") (pinfunction "A_A") (pintype "passive"))
      (node (ref "LED65") (pin "A") (pinfunction "A_A") (pintype "passive"))
      (node (ref "LED66") (pin "A") (pinfunction "A_A") (pintype "passive"))
      (node (ref "LED67") (pin "A") (pinfunction "A_A") (pintype "passive"))
      (node (ref "LED68") (pin "A") (pinfunction "A_A") (pintype "passive"))
      (node (ref "LED69") (pin "A") (pinfunction "A_A") (pintype "passive"))
      (node (ref "LED70") (pin "A") (pinfunction "A_A") (pintype "passive"))
      (node (ref "R12") (pin "2") (pinfunction "2_2") (pintype "passive"))
    )
    (net (code "43") (name "Net-(LED71-PadA)") (class "Default")
      (node (ref "LED71") (pin "A") (pinfunction "A_A") (pintype "passive"))
      (node (ref "LED72") (pin "A") (pinfunction "A_A") (pintype "passive"))
      (node (ref "LED73") (pin "A") (pinfunction "A_A") (pintype "passive"))
      (node (ref "LED74") (pin "A") (pinfunction "A_A") (pintype "passive"))
      (node (ref "LED75") (pin "A") (pinfunction "A_A") (pintype "passive"))
      (node (ref "LED76") (pin "A") (pinfunction "A_A") (pintype "passive"))
      (node (ref "LED77") (pin "A") (pinfunction "A_A") (pintype "passive"))
      (node (ref "LED78") (pin "A") (pinfunction "A_A") (pintype "passive"))
      (node (ref "LED79") (pin "A") (pinfunction "A_A") (pintype "passive"))
      (node (ref "LED80") (pin "A") (pinfunction "A_A") (pintype "passive"))
      (node (ref "R11") (pin "2") (pinfunction "2_2") (pintype "passive"))
    )
    (net (code "44") (name "Net-(Q1-B)") (class "Default")
      (node (ref "Q1") (pin "2") (pinfunction "B_2") (pintype "passive"))
      (node (ref "R1") (pin "2") (pinfunction "2_2") (pintype "passive"))
    )
    (net (code "45") (name "Net-(Q2-B)") (class "Default")
      (node (ref "Q2") (pin "2") (pinfunction "B_2") (pintype "passive"))
      (node (ref "R2") (pin "2") (pinfunction "2_2") (pintype "passive"))
    )
    (net (code "46") (name "Net-(Q3-B)") (class "Default")
      (node (ref "Q3") (pin "2") (pinfunction "B_2") (pintype "passive"))
      (node (ref "R3") (pin "2") (pinfunction "2_2") (pintype "passive"))
    )
    (net (code "47") (name "Net-(Q4-B)") (class "Default")
      (node (ref "Q4") (pin "2") (pinfunction "B_2") (pintype "passive"))
      (node (ref "R4") (pin "2") (pinfunction "2_2") (pintype "passive"))
    )
    (net (code "48") (name "Net-(Q5-B)") (class "Default")
      (node (ref "Q5") (pin "2") (pinfunction "B_2") (pintype "passive"))
      (node (ref "R5") (pin "2") (pinfunction "2_2") (pintype "passive"))
    )
    (net (code "49") (name "Net-(Q6-B)") (class "Default")
      (node (ref "Q6") (pin "2") (pinfunction "B_2") (pintype "passive"))
      (node (ref "R6") (pin "2") (pinfunction "2_2") (pintype "passive"))
    )
    (net (code "50") (name "Net-(Q7-B)") (class "Default")
      (node (ref "Q7") (pin "2") (pinfunction "B_2") (pintype "passive"))
      (node (ref "R7") (pin "2") (pinfunction "2_2") (pintype "passive"))
    )
    (net (code "51") (name "Net-(Q8-B)") (class "Default")
      (node (ref "Q8") (pin "2") (pinfunction "B_2") (pintype "passive"))
      (node (ref "R8") (pin "2") (pinfunction "2_2") (pintype "passive"))
    )
    (net (code "52") (name "Net-(Q9-B)") (class "Default")
      (node (ref "Q9") (pin "2") (pinfunction "B_2") (pintype "passive"))
      (node (ref "R9") (pin "2") (pinfunction "2_2") (pintype "passive"))
    )
    (net (code "53") (name "Net-(Q10-B)") (class "Default")
      (node (ref "Q10") (pin "2") (pinfunction "B_2") (pintype "passive"))
      (node (ref "R10") (pin "2") (pinfunction "2_2") (pintype "passive"))
    )
    (net (code "54") (name "unconnected-(IC1A-CO-Pad12)") (class "Default")
      (node (ref "IC1") (pin "12") (pinfunction "CO_12") (pintype "output"))
    )
    (net (code "55") (name "unconnected-(IC2A-QH*-Pad9)") (class "Default")
      (node (ref "IC2") (pin "9") (pinfunction "QH*_9") (pintype "tri_state"))
    )
  )
)
